# tick-mk-4_6.net
KiCad netlist of a schematic drawn in EAGLE
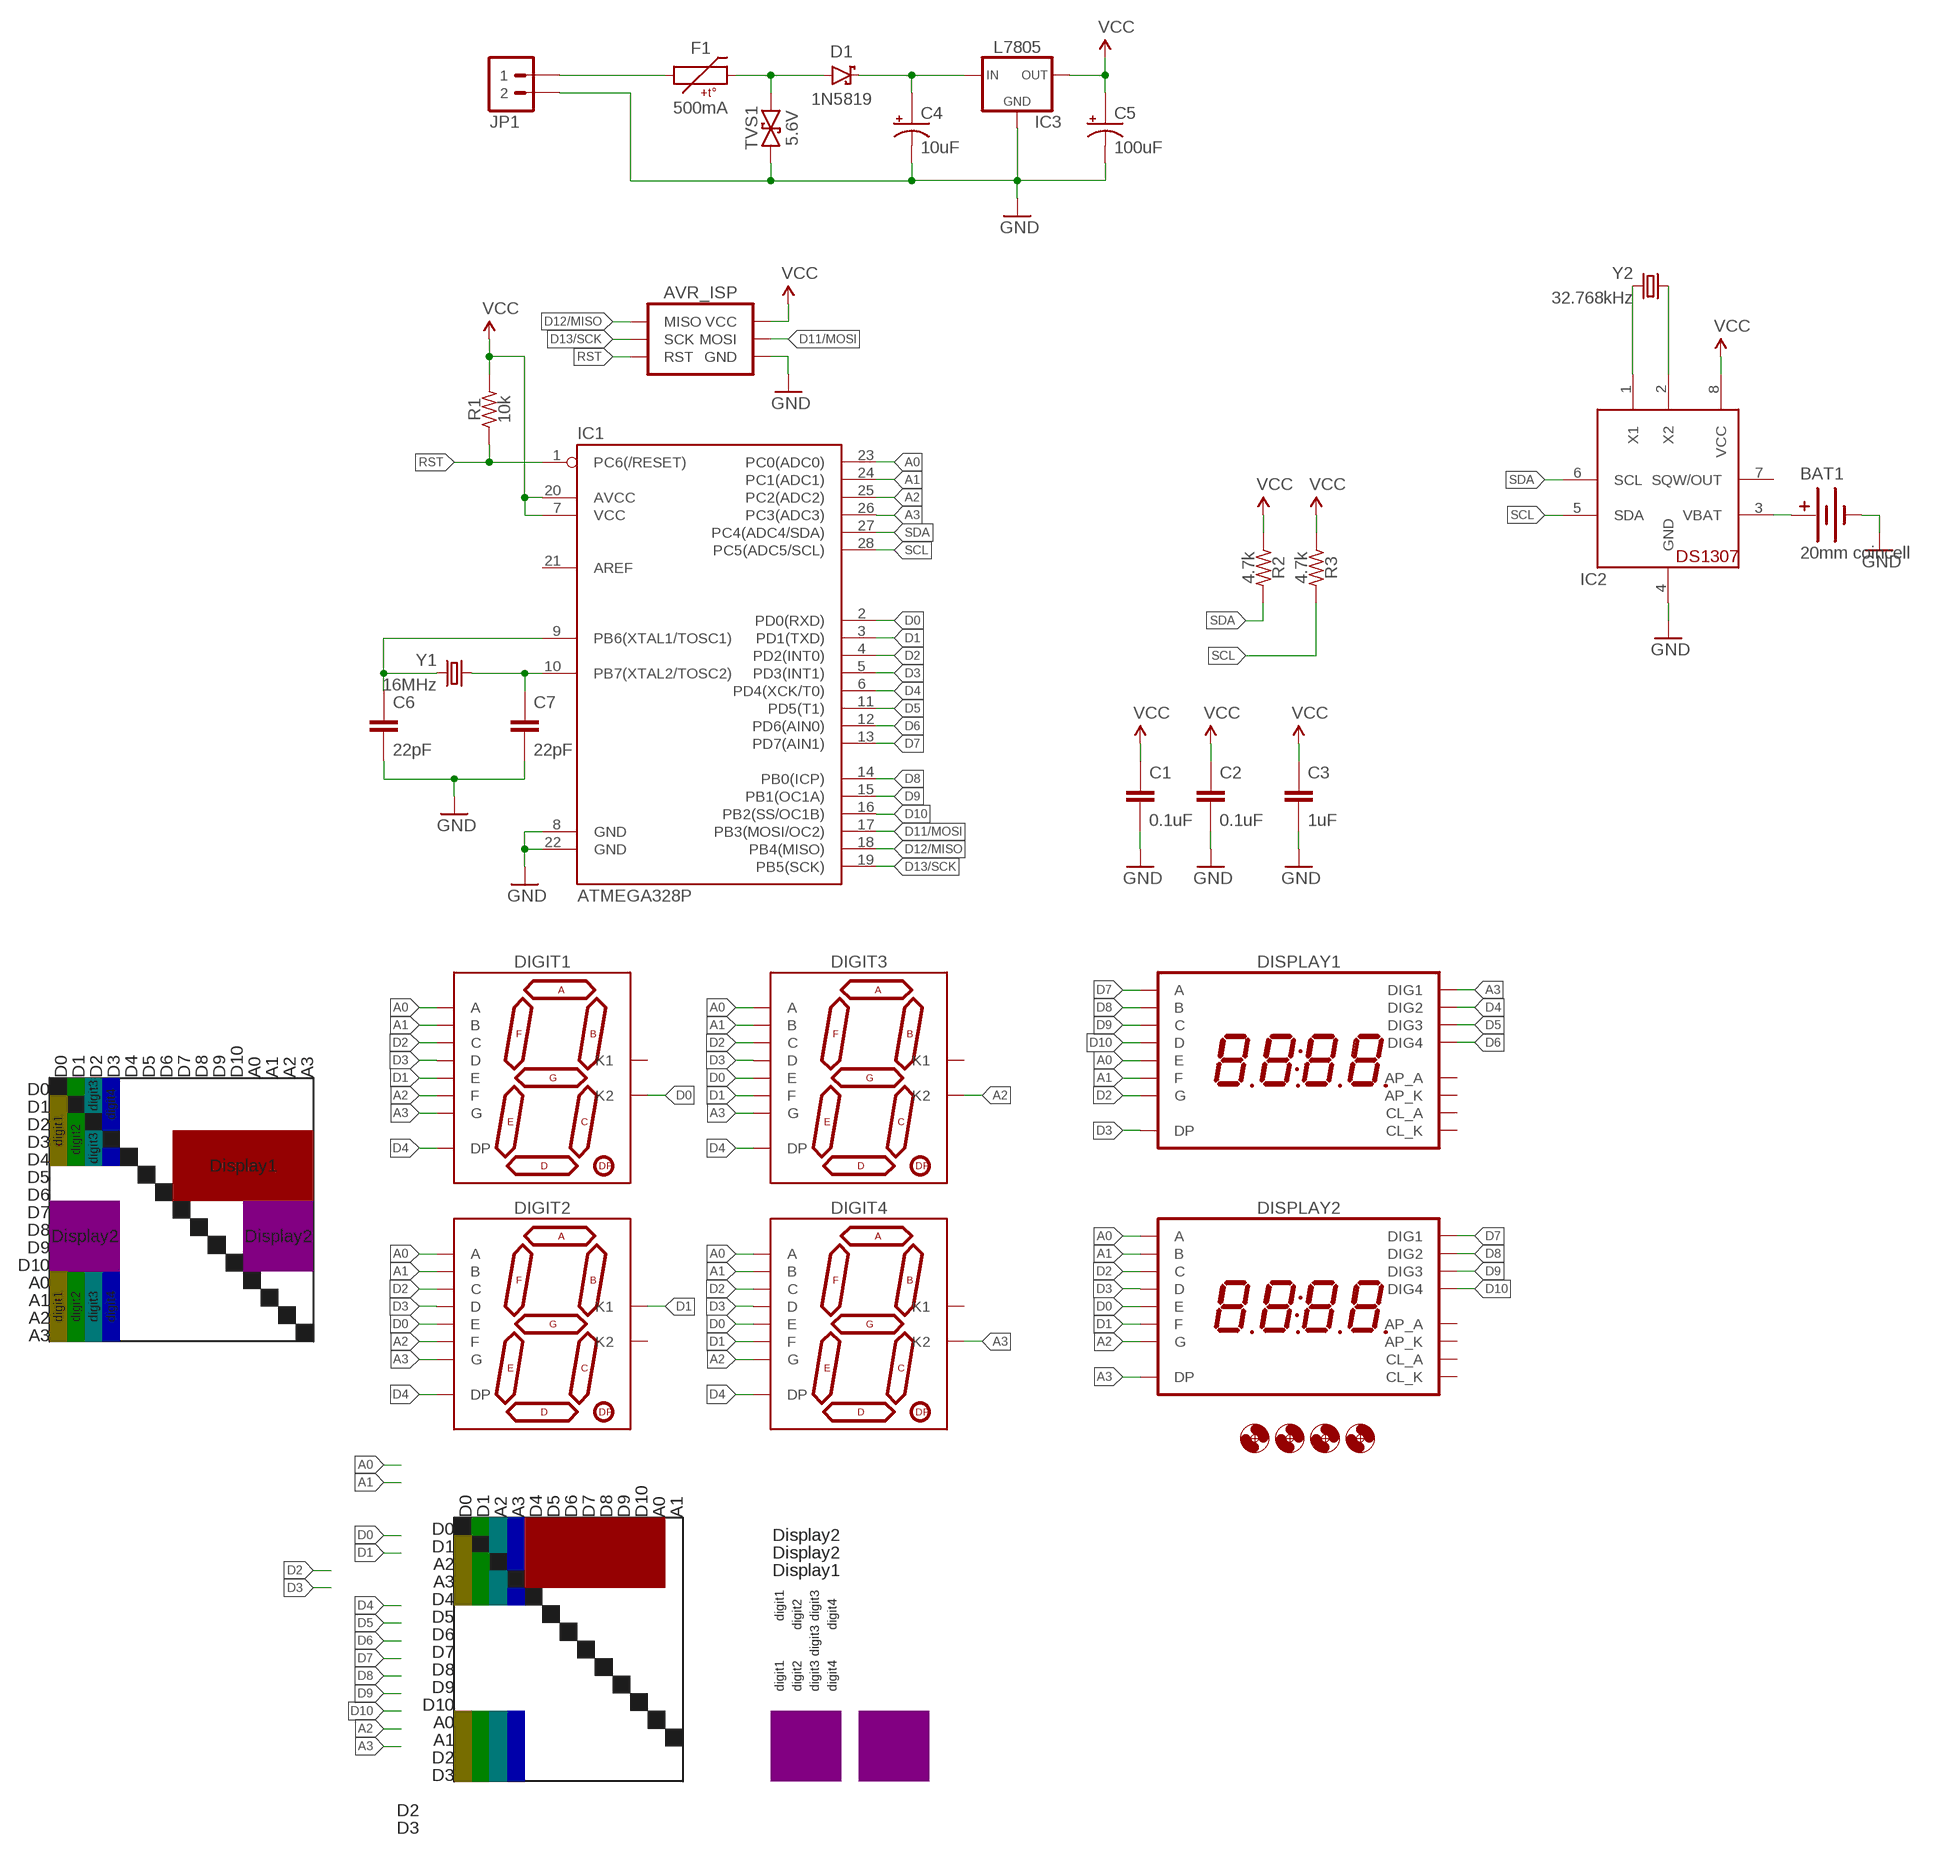
[diagram p0: schematic, sheet 1]

(export (version "E")
  (design (tool "Eeschema 10.0.6"))
  (components
    (comp (ref "AVR_ISP")
      (value "AVR_SPI_PRG_6PTH")
      (footprint "eagle-import:2X3")
      (libsource (lib "eagle-import") (part "AVR_SPI_PRG_6PTH"))
    )
    (comp (ref "BAT1")
      (value "20mm coincell")
      (footprint "eagle-import:BATTCON_20MM_MINE")
      (libsource (lib "eagle-import") (part "BATTERY20MMSMD-MINE"))
    )
    (comp (ref "C1")
      (value "0.1uF")
      (footprint "eagle-import:C025-024X044")
      (libsource (lib "eagle-import") (part "CAPACITOR-CERAMIC025-024X044"))
    )
    (comp (ref "C2")
      (value "0.1uF")
      (footprint "eagle-import:C025-024X044")
      (libsource (lib "eagle-import") (part "CAPACITOR-CERAMIC025-024X044"))
    )
    (comp (ref "C3")
      (value "1uF")
      (footprint "eagle-import:C025-024X044")
      (libsource (lib "eagle-import") (part "CAPACITOR-CERAMIC025-024X044"))
    )
    (comp (ref "C4")
      (value "10uF")
      (footprint "eagle-import:E2-5")
      (libsource (lib "eagle-import") (part "CAPACITOR-POLARIZEDE2-5"))
    )
    (comp (ref "C5")
      (value "100uF")
      (footprint "eagle-import:E2,5-6")
      (libsource (lib "eagle-import") (part "CAPACITOR-POLARIZEDE2.5-6"))
    )
    (comp (ref "C6")
      (value "22pF")
      (footprint "eagle-import:C025-024X044")
      (libsource (lib "eagle-import") (part "CAPACITOR-CERAMIC025-024X044"))
    )
    (comp (ref "C7")
      (value "22pF")
      (footprint "eagle-import:C025-024X044")
      (libsource (lib "eagle-import") (part "CAPACITOR-CERAMIC025-024X044"))
    )
    (comp (ref "D1")
      (value "1N5819")
      (footprint "eagle-import:DIODE-10.16MM")
      (libsource (lib "eagle-import") (part "DIODE-SCHOTTKYPTH-10.16MM"))
    )
    (comp (ref "DIGIT1")
      (value "7SEG_1DIGPTH-25.4MM-BARE")
      (footprint "eagle-import:7SEG_1DIG_25.4MM_NOSILK")
      (libsource (lib "eagle-import") (part "7SEG_1DIGPTH-25.4MM-BARE"))
    )
    (comp (ref "DIGIT2")
      (value "7SEG_1DIGPTH-25.4MM-BARE")
      (footprint "eagle-import:7SEG_1DIG_25.4MM_NOSILK")
      (libsource (lib "eagle-import") (part "7SEG_1DIGPTH-25.4MM-BARE"))
    )
    (comp (ref "DIGIT3")
      (value "7SEG_1DIGPTH-25.4MM-BARE")
      (footprint "eagle-import:7SEG_1DIG_25.4MM_NOSILK")
      (libsource (lib "eagle-import") (part "7SEG_1DIGPTH-25.4MM-BARE"))
    )
    (comp (ref "DIGIT4")
      (value "7SEG_1DIGPTH-25.4MM-BARE")
      (footprint "eagle-import:7SEG_1DIG_25.4MM_NOSILK")
      (libsource (lib "eagle-import") (part "7SEG_1DIGPTH-25.4MM-BARE"))
    )
    (comp (ref "DISPLAY1")
      (value "7SEG_4DIGIT_COLON_APOS")
      (footprint "eagle-import:7SEG_4DIG_10MM")
      (libsource (lib "eagle-import") (part "7SEG_4DIGIT_COLON_APOS"))
    )
    (comp (ref "DISPLAY2")
      (value "7SEG_4DIGIT_COLON_APOS")
      (footprint "eagle-import:7SEG_4DIG_10MM")
      (libsource (lib "eagle-import") (part "7SEG_4DIGIT_COLON_APOS"))
    )
    (comp (ref "F1")
      (value "500mA")
      (footprint "eagle-import:PTC-PTH-5.08MM")
      (libsource (lib "eagle-import") (part "PTCPTH-5.08MM"))
    )
    (comp (ref "H1")
      (value "HOLE#2")
      (footprint "eagle-import:HOLE-#2")
      (libsource (lib "eagle-import") (part "HOLE#2"))
    )
    (comp (ref "H2")
      (value "HOLE#2")
      (footprint "eagle-import:HOLE-#2")
      (libsource (lib "eagle-import") (part "HOLE#2"))
    )
    (comp (ref "H3")
      (value "HOLE#2")
      (footprint "eagle-import:HOLE-#2")
      (libsource (lib "eagle-import") (part "HOLE#2"))
    )
    (comp (ref "H4")
      (value "HOLE#2")
      (footprint "eagle-import:HOLE-#2")
      (libsource (lib "eagle-import") (part "HOLE#2"))
    )
    (comp (ref "IC1")
      (value "ATMEGA328P")
      (footprint "eagle-import:DIL28-3")
      (libsource (lib "eagle-import") (part "ATMEGA328P_PDIP"))
    )
    (comp (ref "IC2")
      (value "DS1307")
      (footprint "eagle-import:DIL08")
      (libsource (lib "eagle-import") (part "DS1307"))
    )
    (comp (ref "IC3")
      (value "L7805")
      (footprint "eagle-import:TO220-IGO-THERMPAD")
      (libsource (lib "eagle-import") (part "V_REG_78XXTO-220-THERMPAD"))
    )
    (comp (ref "JP1")
      (value "M02JST-XH-VERT")
      (footprint "eagle-import:JST-2-XH-VERT-PTH")
      (libsource (lib "eagle-import") (part "M02JST-XH-VERT"))
    )
    (comp (ref "R1")
      (value "10k")
      (footprint "eagle-import:RESISTOR-AXIAL-PTH-7.62MM")
      (libsource (lib "eagle-import") (part "RESISTORPTH-AXIAL-7.62MM"))
    )
    (comp (ref "R2")
      (value "4.7k")
      (footprint "eagle-import:RESISTOR-AXIAL-PTH-7.62MM")
      (libsource (lib "eagle-import") (part "RESISTORPTH-AXIAL-7.62MM"))
    )
    (comp (ref "R3")
      (value "4.7k")
      (footprint "eagle-import:RESISTOR-AXIAL-PTH-7.62MM")
      (libsource (lib "eagle-import") (part "RESISTORPTH-AXIAL-7.62MM"))
    )
    (comp (ref "TVS1")
      (value "5.6V")
      (footprint "eagle-import:DO-41-TVS-BI-10.16MM")
      (libsource (lib "eagle-import") (part "TVSDO-41-10.16MM"))
    )
    (comp (ref "Y1")
      (value "16MHz")
      (footprint "eagle-import:HC49U-V")
      (libsource (lib "eagle-import") (part "CRYSTALHC49UV"))
    )
    (comp (ref "Y2")
      (value "32.768kHz")
      (footprint "eagle-import:TC26H")
      (libsource (lib "eagle-import") (part "CRYSTALTC26H"))
    )
  )
  (nets
    (net (code "1") (name "A0") (class "Default")
      (node (ref "DIGIT1") (pin "7") (pinfunction "A_7") (pintype "bidirectional"))
      (node (ref "DIGIT2") (pin "7") (pinfunction "A_7") (pintype "bidirectional"))
      (node (ref "DIGIT3") (pin "7") (pinfunction "A_7") (pintype "bidirectional"))
      (node (ref "DIGIT4") (pin "7") (pinfunction "A_7") (pintype "bidirectional"))
      (node (ref "DISPLAY1") (pin "5") (pinfunction "E_5") (pintype "passive"))
      (node (ref "DISPLAY2") (pin "14") (pinfunction "A_14") (pintype "passive"))
      (node (ref "IC1") (pin "23") (pinfunction "PC0(ADC0)_23") (pintype "bidirectional"))
    )
    (net (code "2") (name "A1") (class "Default")
      (node (ref "DIGIT1") (pin "6") (pinfunction "B_6") (pintype "bidirectional"))
      (node (ref "DIGIT2") (pin "6") (pinfunction "B_6") (pintype "bidirectional"))
      (node (ref "DIGIT3") (pin "6") (pinfunction "B_6") (pintype "bidirectional"))
      (node (ref "DIGIT4") (pin "6") (pinfunction "B_6") (pintype "bidirectional"))
      (node (ref "DISPLAY1") (pin "11") (pinfunction "F_11") (pintype "passive"))
      (node (ref "DISPLAY2") (pin "16") (pinfunction "B_16") (pintype "passive"))
      (node (ref "IC1") (pin "24") (pinfunction "PC1(ADC1)_24") (pintype "bidirectional"))
    )
    (net (code "3") (name "A2") (class "Default")
      (node (ref "DIGIT1") (pin "9") (pinfunction "F_9") (pintype "bidirectional"))
      (node (ref "DIGIT2") (pin "9") (pinfunction "F_9") (pintype "bidirectional"))
      (node (ref "DIGIT3") (pin "8") (pinfunction "K2_8") (pintype "bidirectional"))
      (node (ref "DIGIT4") (pin "10") (pinfunction "G_10") (pintype "bidirectional"))
      (node (ref "DISPLAY2") (pin "15") (pinfunction "G_15") (pintype "passive"))
      (node (ref "IC1") (pin "25") (pinfunction "PC2(ADC2)_25") (pintype "bidirectional"))
    )
    (net (code "4") (name "A3") (class "Default")
      (node (ref "DIGIT1") (pin "10") (pinfunction "G_10") (pintype "bidirectional"))
      (node (ref "DIGIT2") (pin "10") (pinfunction "G_10") (pintype "bidirectional"))
      (node (ref "DIGIT3") (pin "10") (pinfunction "G_10") (pintype "bidirectional"))
      (node (ref "DIGIT4") (pin "8") (pinfunction "K2_8") (pintype "bidirectional"))
      (node (ref "DISPLAY1") (pin "1") (pinfunction "DIG1_1") (pintype "passive"))
      (node (ref "DISPLAY2") (pin "7") (pinfunction "DP_7") (pintype "passive"))
      (node (ref "IC1") (pin "26") (pinfunction "PC3(ADC3)_26") (pintype "bidirectional"))
    )
    (net (code "5") (name "D0") (class "Default")
      (node (ref "DIGIT1") (pin "8") (pinfunction "K2_8") (pintype "bidirectional"))
      (node (ref "DIGIT2") (pin "1") (pinfunction "E_1") (pintype "bidirectional"))
      (node (ref "DIGIT3") (pin "1") (pinfunction "E_1") (pintype "bidirectional"))
      (node (ref "DIGIT4") (pin "1") (pinfunction "E_1") (pintype "bidirectional"))
      (node (ref "DISPLAY2") (pin "5") (pinfunction "E_5") (pintype "passive"))
      (node (ref "IC1") (pin "2") (pinfunction "PD0(RXD)_2") (pintype "bidirectional"))
    )
    (net (code "6") (name "D1") (class "Default")
      (node (ref "DIGIT1") (pin "1") (pinfunction "E_1") (pintype "bidirectional"))
      (node (ref "DIGIT2") (pin "3") (pinfunction "K1_3") (pintype "bidirectional"))
      (node (ref "DIGIT3") (pin "9") (pinfunction "F_9") (pintype "bidirectional"))
      (node (ref "DIGIT4") (pin "9") (pinfunction "F_9") (pintype "bidirectional"))
      (node (ref "DISPLAY2") (pin "11") (pinfunction "F_11") (pintype "passive"))
      (node (ref "IC1") (pin "3") (pinfunction "PD1(TXD)_3") (pintype "bidirectional"))
    )
    (net (code "7") (name "D2") (class "Default")
      (node (ref "DIGIT1") (pin "4") (pinfunction "C_4") (pintype "bidirectional"))
      (node (ref "DIGIT2") (pin "4") (pinfunction "C_4") (pintype "bidirectional"))
      (node (ref "DIGIT3") (pin "4") (pinfunction "C_4") (pintype "bidirectional"))
      (node (ref "DIGIT4") (pin "4") (pinfunction "C_4") (pintype "bidirectional"))
      (node (ref "DISPLAY1") (pin "15") (pinfunction "G_15") (pintype "passive"))
      (node (ref "DISPLAY2") (pin "13") (pinfunction "C_13") (pintype "passive"))
      (node (ref "IC1") (pin "4") (pinfunction "PD2(INT0)_4") (pintype "bidirectional"))
    )
    (net (code "8") (name "D3") (class "Default")
      (node (ref "DIGIT1") (pin "2") (pinfunction "D_2") (pintype "bidirectional"))
      (node (ref "DIGIT2") (pin "2") (pinfunction "D_2") (pintype "bidirectional"))
      (node (ref "DIGIT3") (pin "2") (pinfunction "D_2") (pintype "bidirectional"))
      (node (ref "DIGIT4") (pin "2") (pinfunction "D_2") (pintype "bidirectional"))
      (node (ref "DISPLAY1") (pin "7") (pinfunction "DP_7") (pintype "passive"))
      (node (ref "DISPLAY2") (pin "3") (pinfunction "D_3") (pintype "passive"))
      (node (ref "IC1") (pin "5") (pinfunction "PD3(INT1)_5") (pintype "bidirectional"))
    )
    (net (code "9") (name "D4") (class "Default")
      (node (ref "DIGIT1") (pin "5") (pinfunction "DP_5") (pintype "bidirectional"))
      (node (ref "DIGIT2") (pin "5") (pinfunction "DP_5") (pintype "bidirectional"))
      (node (ref "DIGIT3") (pin "5") (pinfunction "DP_5") (pintype "bidirectional"))
      (node (ref "DIGIT4") (pin "5") (pinfunction "DP_5") (pintype "bidirectional"))
      (node (ref "DISPLAY1") (pin "2") (pinfunction "DIG2_2") (pintype "passive"))
      (node (ref "IC1") (pin "6") (pinfunction "PD4(XCK/T0)_6") (pintype "bidirectional"))
    )
    (net (code "10") (name "D5") (class "Default")
      (node (ref "DISPLAY1") (pin "6") (pinfunction "DIG3_6") (pintype "passive"))
      (node (ref "IC1") (pin "11") (pinfunction "PD5(T1)_11") (pintype "bidirectional"))
    )
    (net (code "11") (name "D6") (class "Default")
      (node (ref "DISPLAY1") (pin "8") (pinfunction "DIG4_8") (pintype "passive"))
      (node (ref "IC1") (pin "12") (pinfunction "PD6(AIN0)_12") (pintype "bidirectional"))
    )
    (net (code "12") (name "D7") (class "Default")
      (node (ref "DISPLAY1") (pin "14") (pinfunction "A_14") (pintype "passive"))
      (node (ref "DISPLAY2") (pin "1") (pinfunction "DIG1_1") (pintype "passive"))
      (node (ref "IC1") (pin "13") (pinfunction "PD7(AIN1)_13") (pintype "bidirectional"))
    )
    (net (code "13") (name "D8") (class "Default")
      (node (ref "DISPLAY1") (pin "16") (pinfunction "B_16") (pintype "passive"))
      (node (ref "DISPLAY2") (pin "2") (pinfunction "DIG2_2") (pintype "passive"))
      (node (ref "IC1") (pin "14") (pinfunction "PB0(ICP)_14") (pintype "bidirectional"))
    )
    (net (code "14") (name "D9") (class "Default")
      (node (ref "DISPLAY1") (pin "13") (pinfunction "C_13") (pintype "passive"))
      (node (ref "DISPLAY2") (pin "6") (pinfunction "DIG3_6") (pintype "passive"))
      (node (ref "IC1") (pin "15") (pinfunction "PB1(OC1A)_15") (pintype "bidirectional"))
    )
    (net (code "15") (name "D10") (class "Default")
      (node (ref "DISPLAY1") (pin "3") (pinfunction "D_3") (pintype "passive"))
      (node (ref "DISPLAY2") (pin "8") (pinfunction "DIG4_8") (pintype "passive"))
      (node (ref "IC1") (pin "16") (pinfunction "PB2(SS/OC1B)_16") (pintype "bidirectional"))
    )
    (net (code "16") (name "D11{slash}MOSI") (class "Default")
      (node (ref "AVR_ISP") (pin "4") (pinfunction "MOSI_4") (pintype "passive"))
      (node (ref "IC1") (pin "17") (pinfunction "PB3(MOSI/OC2)_17") (pintype "bidirectional"))
    )
    (net (code "17") (name "D12{slash}MISO") (class "Default")
      (node (ref "AVR_ISP") (pin "1") (pinfunction "MISO_1") (pintype "passive"))
      (node (ref "IC1") (pin "18") (pinfunction "PB4(MISO)_18") (pintype "bidirectional"))
    )
    (net (code "18") (name "D13{slash}SCK") (class "Default")
      (node (ref "AVR_ISP") (pin "3") (pinfunction "SCK_3") (pintype "passive"))
      (node (ref "IC1") (pin "19") (pinfunction "PB5(SCK)_19") (pintype "bidirectional"))
    )
    (net (code "19") (name "GND") (class "Default")
      (node (ref "AVR_ISP") (pin "6") (pinfunction "GND_6") (pintype "passive"))
      (node (ref "BAT1") (pin "BOTTOM") (pinfunction "-_BOTTOM") (pintype "power_in"))
      (node (ref "C1") (pin "2") (pinfunction "2_2") (pintype "passive"))
      (node (ref "C2") (pin "2") (pinfunction "2_2") (pintype "passive"))
      (node (ref "C3") (pin "2") (pinfunction "2_2") (pintype "passive"))
      (node (ref "C4") (pin "-") (pinfunction "-_-") (pintype "passive"))
      (node (ref "C5") (pin "-") (pinfunction "-_-") (pintype "passive"))
      (node (ref "C6") (pin "2") (pinfunction "2_2") (pintype "passive"))
      (node (ref "C7") (pin "2") (pinfunction "2_2") (pintype "passive"))
      (node (ref "IC1") (pin "22") (pinfunction "GND_22") (pintype "bidirectional"))
      (node (ref "IC1") (pin "8") (pinfunction "GND_8") (pintype "bidirectional"))
      (node (ref "IC2") (pin "4") (pinfunction "GND_4") (pintype "power_in"))
      (node (ref "IC3") (pin "4") (pinfunction "GND_4") (pintype "bidirectional"))
      (node (ref "IC3") (pin "GND") (pinfunction "GND_GND") (pintype "bidirectional"))
      (node (ref "JP1") (pin "2") (pinfunction "2_2") (pintype "passive"))
      (node (ref "TVS1") (pin "P$1") (pinfunction "1_P$1") (pintype "passive"))
    )
    (net (code "20") (name "Net-(C4-Pad+)") (class "Default")
      (node (ref "C4") (pin "+") (pinfunction "+_+") (pintype "passive"))
      (node (ref "D1") (pin "C") (pinfunction "C_C") (pintype "passive"))
      (node (ref "IC3") (pin "IN") (pinfunction "IN_IN") (pintype "bidirectional"))
    )
    (net (code "21") (name "Net-(F1-1)") (class "Default")
      (node (ref "F1") (pin "P$1") (pinfunction "1_P$1") (pintype "passive"))
      (node (ref "JP1") (pin "1") (pinfunction "1_1") (pintype "passive"))
    )
    (net (code "22") (name "Net-(F1-2)") (class "Default")
      (node (ref "D1") (pin "A") (pinfunction "A_A") (pintype "passive"))
      (node (ref "F1") (pin "P$2") (pinfunction "2_P$2") (pintype "passive"))
      (node (ref "TVS1") (pin "P$2") (pinfunction "2_P$2") (pintype "passive"))
    )
    (net (code "23") (name "Net-(IC1-PB6(XTAL1{slash}TOSC1))") (class "Default")
      (node (ref "C6") (pin "1") (pinfunction "1_1") (pintype "passive"))
      (node (ref "IC1") (pin "9") (pinfunction "PB6(XTAL1/TOSC1)_9") (pintype "bidirectional"))
      (node (ref "Y1") (pin "2") (pinfunction "2_2") (pintype "passive"))
    )
    (net (code "24") (name "Net-(IC1-PB7(XTAL2{slash}TOSC2))") (class "Default")
      (node (ref "C7") (pin "1") (pinfunction "1_1") (pintype "passive"))
      (node (ref "IC1") (pin "10") (pinfunction "PB7(XTAL2/TOSC2)_10") (pintype "bidirectional"))
      (node (ref "Y1") (pin "1") (pinfunction "1_1") (pintype "passive"))
    )
    (net (code "25") (name "Net-(IC2-VBAT)") (class "Default")
      (node (ref "BAT1") (pin "TOP@1") (pinfunction "+_TOP@1") (pintype "power_in"))
      (node (ref "BAT1") (pin "TOP@2") (pinfunction "+_TOP@2") (pintype "power_in"))
      (node (ref "IC2") (pin "3") (pinfunction "VBAT_3") (pintype "power_in"))
    )
    (net (code "26") (name "Net-(IC2-X1)") (class "Default")
      (node (ref "IC2") (pin "1") (pinfunction "X1_1") (pintype "passive"))
      (node (ref "Y2") (pin "2") (pinfunction "2_2") (pintype "passive"))
    )
    (net (code "27") (name "Net-(IC2-X2)") (class "Default")
      (node (ref "IC2") (pin "2") (pinfunction "X2_2") (pintype "passive"))
      (node (ref "Y2") (pin "1") (pinfunction "1_1") (pintype "passive"))
    )
    (net (code "28") (name "RST") (class "Default")
      (node (ref "AVR_ISP") (pin "5") (pinfunction "RST_5") (pintype "passive"))
      (node (ref "IC1") (pin "1") (pinfunction "PC6(/RESET)_1") (pintype "bidirectional"))
      (node (ref "R1") (pin "P$1") (pinfunction "1_P$1") (pintype "passive"))
    )
    (net (code "29") (name "SCL") (class "Default")
      (node (ref "IC1") (pin "28") (pinfunction "PC5(ADC5/SCL)_28") (pintype "bidirectional"))
      (node (ref "IC2") (pin "5") (pinfunction "SDA_5") (pintype "bidirectional"))
      (node (ref "R3") (pin "P$2") (pinfunction "2_P$2") (pintype "passive"))
    )
    (net (code "30") (name "SDA") (class "Default")
      (node (ref "IC1") (pin "27") (pinfunction "PC4(ADC4/SDA)_27") (pintype "bidirectional"))
      (node (ref "IC2") (pin "6") (pinfunction "SCL_6") (pintype "bidirectional"))
      (node (ref "R2") (pin "P$2") (pinfunction "2_P$2") (pintype "passive"))
    )
    (net (code "31") (name "VCC") (class "Default")
      (node (ref "AVR_ISP") (pin "2") (pinfunction "VCC_2") (pintype "passive"))
      (node (ref "C1") (pin "1") (pinfunction "1_1") (pintype "passive"))
      (node (ref "C2") (pin "1") (pinfunction "1_1") (pintype "passive"))
      (node (ref "C3") (pin "1") (pinfunction "1_1") (pintype "passive"))
      (node (ref "C5") (pin "+") (pinfunction "+_+") (pintype "passive"))
      (node (ref "IC1") (pin "20") (pinfunction "AVCC_20") (pintype "bidirectional"))
      (node (ref "IC1") (pin "7") (pinfunction "VCC_7") (pintype "bidirectional"))
      (node (ref "IC2") (pin "8") (pinfunction "VCC_8") (pintype "power_in"))
      (node (ref "IC3") (pin "OUT") (pinfunction "OUT_OUT") (pintype "bidirectional"))
      (node (ref "R1") (pin "P$2") (pinfunction "2_P$2") (pintype "passive"))
      (node (ref "R2") (pin "P$1") (pinfunction "1_P$1") (pintype "passive"))
      (node (ref "R3") (pin "P$1") (pinfunction "1_P$1") (pintype "passive"))
    )
    (net (code "32") (name "unconnected-(DIGIT1-K1-Pad3)") (class "Default")
      (node (ref "DIGIT1") (pin "3") (pinfunction "K1_3") (pintype "bidirectional"))
    )
    (net (code "33") (name "unconnected-(DIGIT2-K2-Pad8)") (class "Default")
      (node (ref "DIGIT2") (pin "8") (pinfunction "K2_8") (pintype "bidirectional"))
    )
    (net (code "34") (name "unconnected-(DIGIT3-K1-Pad3)") (class "Default")
      (node (ref "DIGIT3") (pin "3") (pinfunction "K1_3") (pintype "bidirectional"))
    )
    (net (code "35") (name "unconnected-(DIGIT4-K1-Pad3)") (class "Default")
      (node (ref "DIGIT4") (pin "3") (pinfunction "K1_3") (pintype "bidirectional"))
    )
    (net (code "36") (name "unconnected-(DISPLAY1-AP_A-Pad10)") (class "Default")
      (node (ref "DISPLAY1") (pin "10") (pinfunction "AP_A_10") (pintype "bidirectional"))
    )
    (net (code "37") (name "unconnected-(DISPLAY1-AP_K-Pad9)") (class "Default")
      (node (ref "DISPLAY1") (pin "9") (pinfunction "AP_K_9") (pintype "bidirectional"))
    )
    (net (code "38") (name "unconnected-(DISPLAY1-CL_A-Pad4)") (class "Default")
      (node (ref "DISPLAY1") (pin "4") (pinfunction "CL_A_4") (pintype "passive"))
    )
    (net (code "39") (name "unconnected-(DISPLAY1-CL_K-Pad12)") (class "Default")
      (node (ref "DISPLAY1") (pin "12") (pinfunction "CL_K_12") (pintype "passive"))
    )
    (net (code "40") (name "unconnected-(DISPLAY2-AP_A-Pad10)") (class "Default")
      (node (ref "DISPLAY2") (pin "10") (pinfunction "AP_A_10") (pintype "bidirectional"))
    )
    (net (code "41") (name "unconnected-(DISPLAY2-AP_K-Pad9)") (class "Default")
      (node (ref "DISPLAY2") (pin "9") (pinfunction "AP_K_9") (pintype "bidirectional"))
    )
    (net (code "42") (name "unconnected-(DISPLAY2-CL_A-Pad4)") (class "Default")
      (node (ref "DISPLAY2") (pin "4") (pinfunction "CL_A_4") (pintype "passive"))
    )
    (net (code "43") (name "unconnected-(DISPLAY2-CL_K-Pad12)") (class "Default")
      (node (ref "DISPLAY2") (pin "12") (pinfunction "CL_K_12") (pintype "passive"))
    )
    (net (code "44") (name "unconnected-(IC1-AREF-Pad21)") (class "Default")
      (node (ref "IC1") (pin "21") (pinfunction "AREF_21") (pintype "bidirectional"))
    )
    (net (code "45") (name "unconnected-(IC2-SQW{slash}OUT-Pad7)") (class "Default")
      (node (ref "IC2") (pin "7") (pinfunction "SQW/OUT_7") (pintype "bidirectional"))
    )
  )
)
